# sch3.net
KiCad netlist of a schematic drawn in Altium Designer
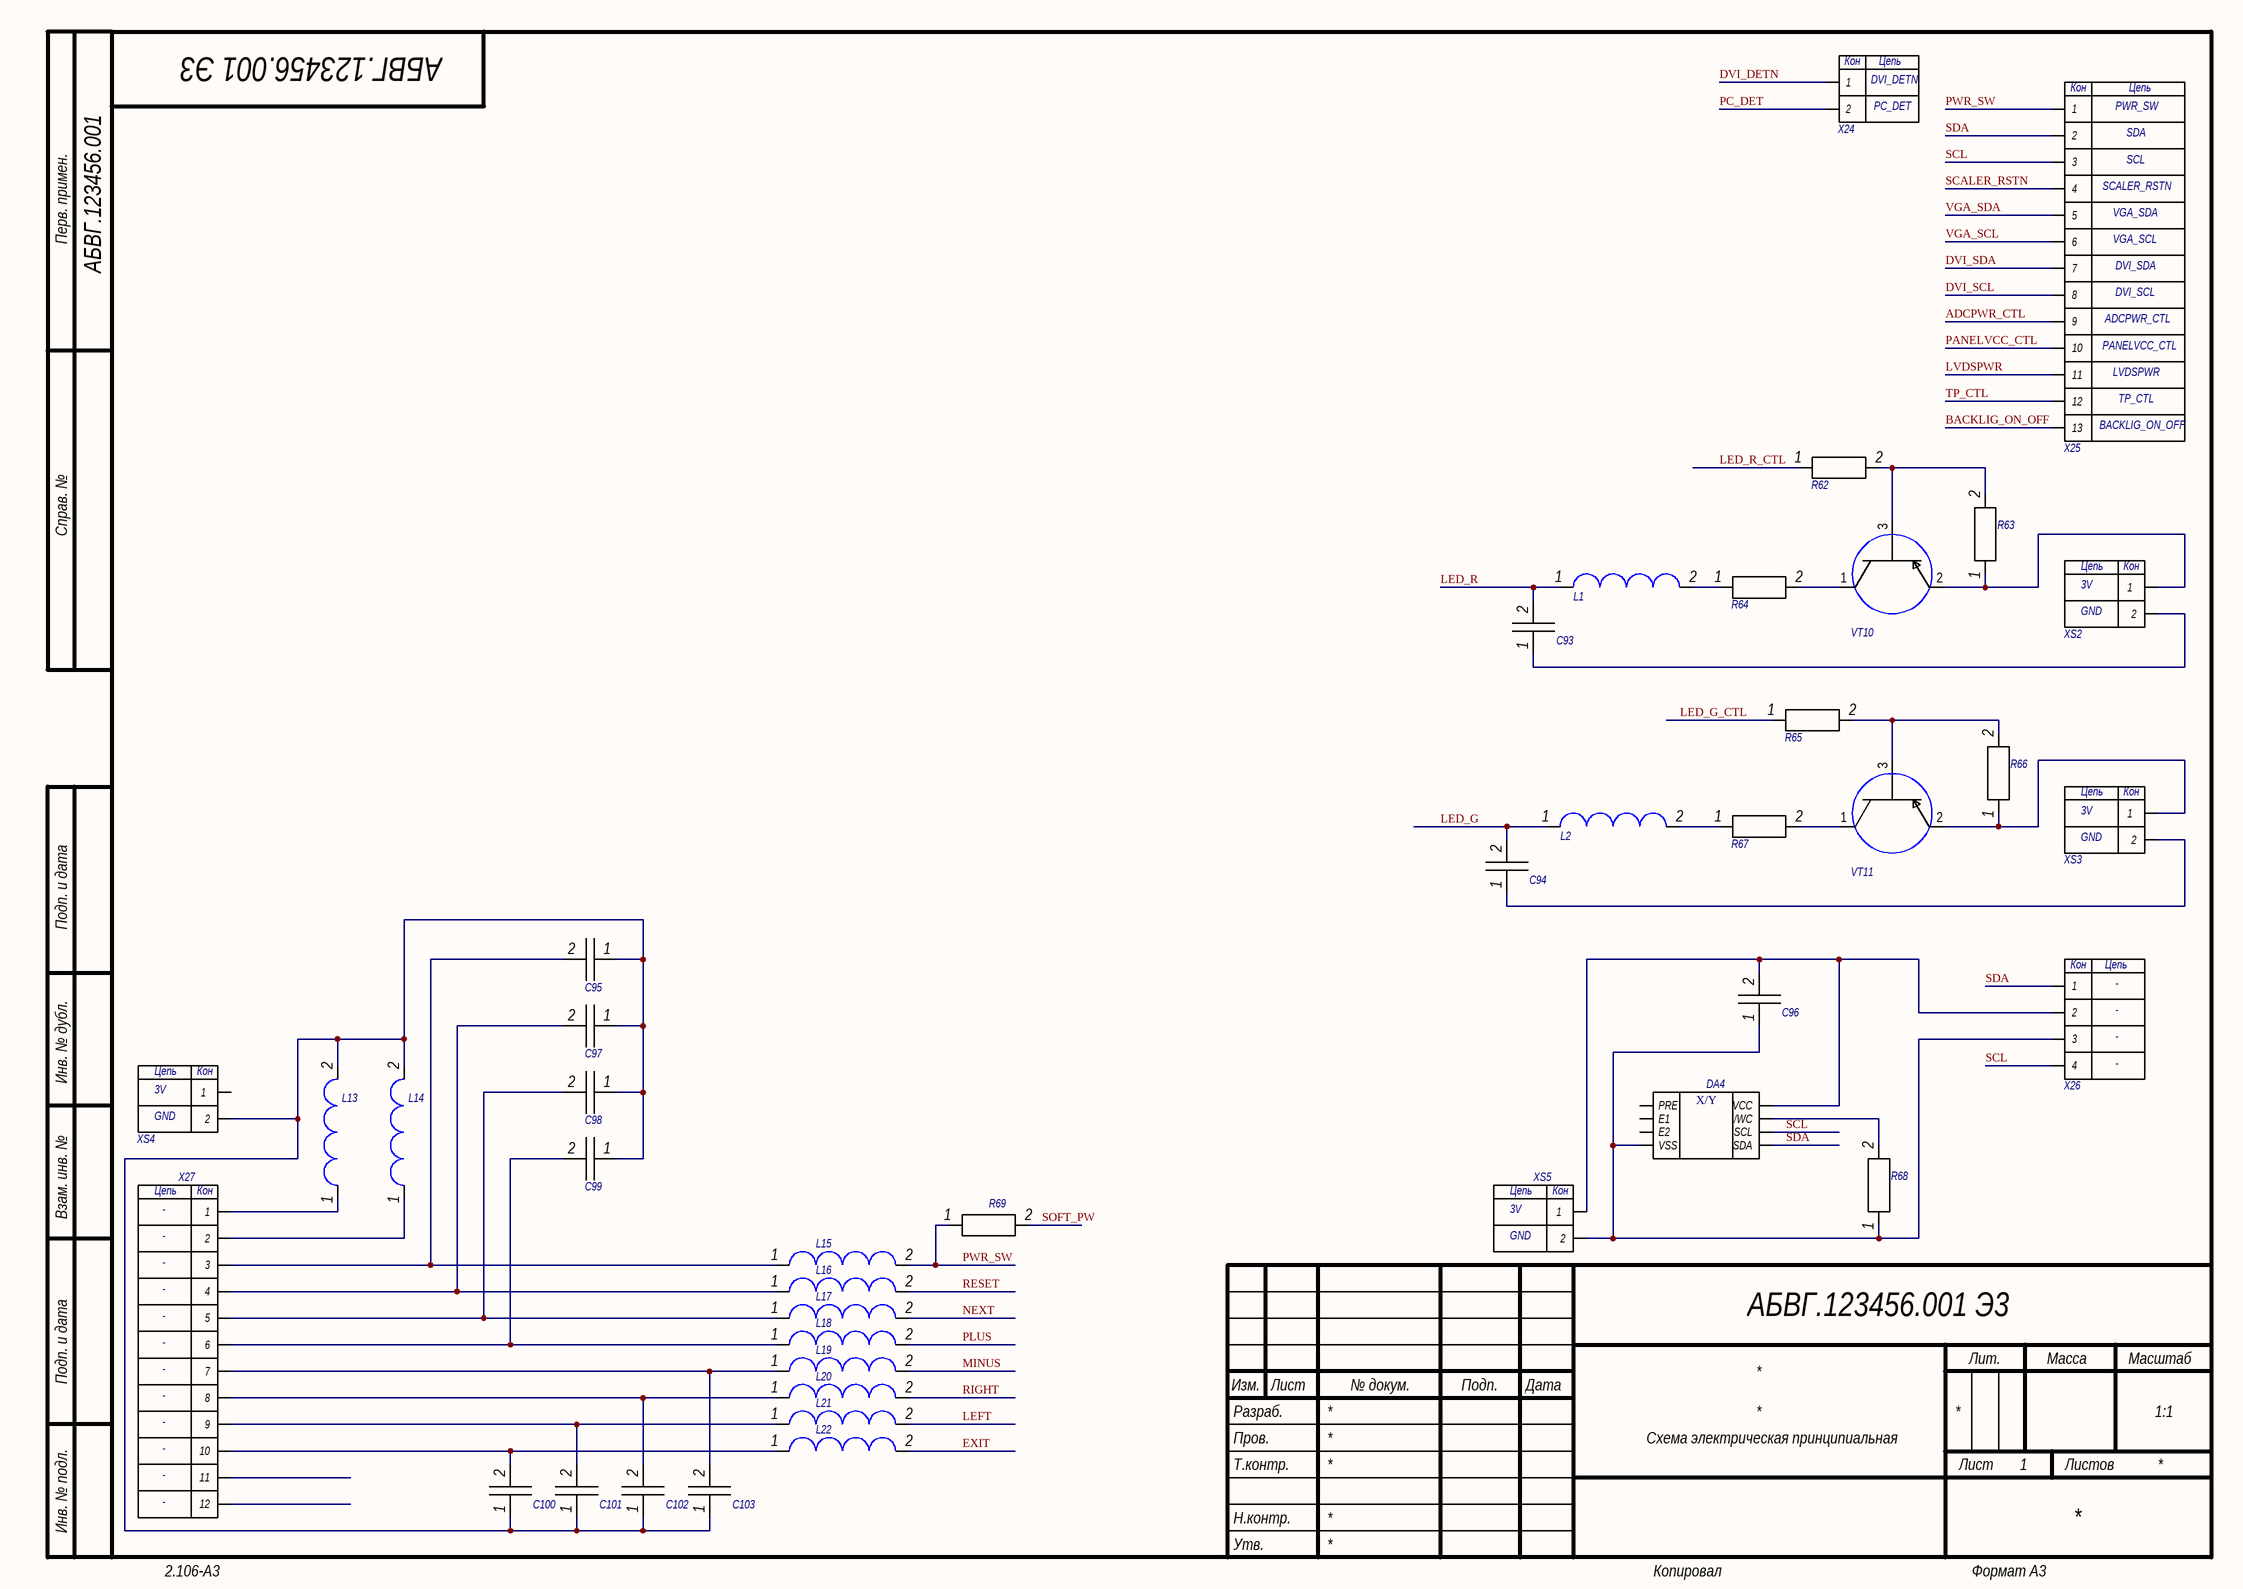
[diagram p0: sch3.SchDoc]

(export (version "E")
  (design (tool "Eeschema 10.0.6"))
  (components
    (comp (ref "C93")
      (value "*")
      (footprint "Capacitor 0805")
      (libsource (lib "k7shared") (part "Capacitor"))
    )
    (comp (ref "C94")
      (value "*")
      (footprint "Capacitor 0805")
      (libsource (lib "k7shared") (part "Capacitor"))
    )
    (comp (ref "C95")
      (value "*")
      (footprint "Capacitor 0805")
      (libsource (lib "k7shared") (part "Capacitor"))
    )
    (comp (ref "C96")
      (value "*")
      (footprint "Capacitor 0805")
      (libsource (lib "k7shared") (part "Capacitor"))
    )
    (comp (ref "C97")
      (value "*")
      (footprint "Capacitor 0805")
      (libsource (lib "k7shared") (part "Capacitor"))
    )
    (comp (ref "C98")
      (value "*")
      (footprint "Capacitor 0805")
      (libsource (lib "k7shared") (part "Capacitor"))
    )
    (comp (ref "C99")
      (value "*")
      (footprint "Capacitor 0805")
      (libsource (lib "k7shared") (part "Capacitor"))
    )
    (comp (ref "C100")
      (value "*")
      (footprint "Capacitor 0805")
      (libsource (lib "k7shared") (part "Capacitor"))
    )
    (comp (ref "C101")
      (value "*")
      (footprint "Capacitor 0805")
      (libsource (lib "k7shared") (part "Capacitor"))
    )
    (comp (ref "C102")
      (value "*")
      (footprint "Capacitor 0805")
      (libsource (lib "k7shared") (part "Capacitor"))
    )
    (comp (ref "C103")
      (value "*")
      (footprint "Capacitor 0805")
      (libsource (lib "k7shared") (part "Capacitor"))
    )
    (comp (ref "DA4") (value "*") (footprint "IC102") (libsource (lib "k7sch3") (part "IC102")))
    (comp (ref "L1") (value "*") (footprint "Inductor 2520") (libsource (lib "k7shared") (part "Inductor")))
    (comp (ref "L2") (value "*") (footprint "Inductor 2520") (libsource (lib "k7shared") (part "Inductor")))
    (comp (ref "L13") (value "*") (footprint "Inductor 2520") (libsource (lib "") (part "Inductor_1")))
    (comp (ref "L14") (value "*") (footprint "Inductor 2520") (libsource (lib "") (part "Inductor_1")))
    (comp (ref "L15") (value "*") (footprint "Inductor 2520") (libsource (lib "k7shared") (part "Inductor")))
    (comp (ref "L16") (value "*") (footprint "Inductor 2520") (libsource (lib "k7shared") (part "Inductor")))
    (comp (ref "L17") (value "*") (footprint "Inductor 2520") (libsource (lib "k7shared") (part "Inductor")))
    (comp (ref "L18") (value "*") (footprint "Inductor 2520") (libsource (lib "k7shared") (part "Inductor")))
    (comp (ref "L19") (value "*") (footprint "Inductor 2520") (libsource (lib "k7shared") (part "Inductor")))
    (comp (ref "L20") (value "*") (footprint "Inductor 2520") (libsource (lib "k7shared") (part "Inductor")))
    (comp (ref "L21") (value "*") (footprint "Inductor 2520") (libsource (lib "k7shared") (part "Inductor")))
    (comp (ref "L22") (value "*") (footprint "Inductor 2520") (libsource (lib "k7shared") (part "Inductor")))
    (comp (ref "R62") (value "*") (footprint "Resistor 1206") (libsource (lib "k7shared") (part "Resistor")))
    (comp (ref "R63") (value "*") (footprint "Resistor 1206") (libsource (lib "k7shared") (part "Resistor")))
    (comp (ref "R64") (value "*") (footprint "Resistor 1206") (libsource (lib "k7shared") (part "Resistor")))
    (comp (ref "R65") (value "*") (footprint "Resistor 1206") (libsource (lib "k7shared") (part "Resistor")))
    (comp (ref "R66") (value "*") (footprint "Resistor 1206") (libsource (lib "k7shared") (part "Resistor")))
    (comp (ref "R67") (value "*") (footprint "Resistor 1206") (libsource (lib "k7shared") (part "Resistor")))
    (comp (ref "R68") (value "*") (footprint "Resistor 1206") (libsource (lib "k7shared") (part "Resistor")))
    (comp (ref "R69") (value "*") (footprint "Resistor 1206") (libsource (lib "k7shared") (part "Resistor")))
    (comp (ref "VT10")
      (value "*")
      (footprint "Transistor 1")
      (libsource (lib "k7shared") (part "Transistor 2"))
    )
    (comp (ref "VT11")
      (value "*")
      (footprint "Transistor 1")
      (libsource (lib "k7shared") (part "Transistor 2"))
    )
    (comp (ref "X24") (value "*") (footprint "Inputs") (libsource (lib "k7sch3") (part "Inputs")))
    (comp (ref "X25") (value "*") (footprint "Outputs") (libsource (lib "k7sch3") (part "Outputs")))
    (comp (ref "X26") (value "*") (footprint "J102") (libsource (lib "k7sch3") (part "J102")))
    (comp (ref "X27") (value "*") (footprint "J101") (libsource (lib "k7sch3") (part "J101")))
    (comp (ref "XS2") (value "*") (footprint "VCC-GND") (libsource (lib "k7shared") (part "VCC-GND R")))
    (comp (ref "XS3") (value "*") (footprint "VCC-GND") (libsource (lib "k7shared") (part "VCC-GND R")))
    (comp (ref "XS4") (value "*") (footprint "VCC-GND") (libsource (lib "k7shared") (part "VCC-GND R")))
    (comp (ref "XS5") (value "*") (footprint "VCC-GND") (libsource (lib "k7shared") (part "VCC-GND R")))
  )
  (nets
    (net (code "1") (name "/ADCPWR_CTL") (class "Default")
      (node (ref "X25") (pin "9") (pinfunction "9_9") (pintype "passive"))
    )
    (net (code "2") (name "/BACKLIG_ON_OFF") (class "Default")
      (node (ref "X25") (pin "13") (pinfunction "13_13") (pintype "passive"))
    )
    (net (code "3") (name "/DVI_DETN") (class "Default")
      (node (ref "X24") (pin "1") (pinfunction "1_1") (pintype "passive"))
    )
    (net (code "4") (name "/DVI_SCL") (class "Default")
      (node (ref "X25") (pin "8") (pinfunction "8_8") (pintype "passive"))
    )
    (net (code "5") (name "/DVI_SDA") (class "Default")
      (node (ref "X25") (pin "7") (pinfunction "7_7") (pintype "passive"))
    )
    (net (code "6") (name "/EXIT") (class "Default")
      (node (ref "L22") (pin "2") (pinfunction "2_2") (pintype "passive"))
    )
    (net (code "7") (name "/LED_G") (class "Default")
      (node (ref "C94") (pin "2") (pinfunction "2_2") (pintype "passive"))
      (node (ref "L2") (pin "1") (pinfunction "1_1") (pintype "passive"))
    )
    (net (code "8") (name "/LED_G_CTL") (class "Default")
      (node (ref "R65") (pin "1") (pinfunction "1_1") (pintype "passive"))
    )
    (net (code "9") (name "/LED_R") (class "Default")
      (node (ref "C93") (pin "2") (pinfunction "2_2") (pintype "passive"))
      (node (ref "L1") (pin "1") (pinfunction "1_1") (pintype "passive"))
    )
    (net (code "10") (name "/LED_R_CTL") (class "Default")
      (node (ref "R62") (pin "1") (pinfunction "1_1") (pintype "passive"))
    )
    (net (code "11") (name "/LEFT") (class "Default")
      (node (ref "L21") (pin "2") (pinfunction "2_2") (pintype "passive"))
    )
    (net (code "12") (name "/LVDSPWR") (class "Default")
      (node (ref "X25") (pin "11") (pinfunction "11_11") (pintype "passive"))
    )
    (net (code "13") (name "/MINUS") (class "Default")
      (node (ref "L19") (pin "2") (pinfunction "2_2") (pintype "passive"))
    )
    (net (code "14") (name "/NEXT") (class "Default")
      (node (ref "L17") (pin "2") (pinfunction "2_2") (pintype "passive"))
    )
    (net (code "15") (name "/PANELVCC_CTL") (class "Default")
      (node (ref "X25") (pin "10") (pinfunction "10_10") (pintype "passive"))
    )
    (net (code "16") (name "/PC_DET") (class "Default")
      (node (ref "X24") (pin "2") (pinfunction "2_2") (pintype "passive"))
    )
    (net (code "17") (name "/PLUS") (class "Default")
      (node (ref "L18") (pin "2") (pinfunction "2_2") (pintype "passive"))
    )
    (net (code "18") (name "/PWR_SW") (class "Default")
      (node (ref "L15") (pin "2") (pinfunction "2_2") (pintype "passive"))
      (node (ref "R69") (pin "1") (pinfunction "1_1") (pintype "passive"))
      (node (ref "X25") (pin "1") (pinfunction "1_1") (pintype "passive"))
    )
    (net (code "19") (name "/RESET") (class "Default")
      (node (ref "L16") (pin "2") (pinfunction "2_2") (pintype "passive"))
    )
    (net (code "20") (name "/RIGHT") (class "Default")
      (node (ref "L20") (pin "2") (pinfunction "2_2") (pintype "passive"))
    )
    (net (code "21") (name "/SCALER_RSTN") (class "Default")
      (node (ref "X25") (pin "4") (pinfunction "4_4") (pintype "passive"))
    )
    (net (code "22") (name "/SCL") (class "Default")
      (node (ref "DA4") (pin "7") (pinfunction "SCL_7") (pintype "passive"))
      (node (ref "X25") (pin "3") (pinfunction "3_3") (pintype "passive"))
      (node (ref "X26") (pin "4") (pinfunction "4_4") (pintype "passive"))
    )
    (net (code "23") (name "/SDA") (class "Default")
      (node (ref "DA4") (pin "8") (pinfunction "SDA_8") (pintype "passive"))
      (node (ref "X25") (pin "2") (pinfunction "2_2") (pintype "passive"))
      (node (ref "X26") (pin "1") (pinfunction "1_1") (pintype "passive"))
    )
    (net (code "24") (name "/SOFT_PW") (class "Default")
      (node (ref "R69") (pin "2") (pinfunction "2_2") (pintype "passive"))
    )
    (net (code "25") (name "/TP_CTL") (class "Default")
      (node (ref "X25") (pin "12") (pinfunction "12_12") (pintype "passive"))
    )
    (net (code "26") (name "/VGA_SCL") (class "Default")
      (node (ref "X25") (pin "6") (pinfunction "6_6") (pintype "passive"))
    )
    (net (code "27") (name "/VGA_SDA") (class "Default")
      (node (ref "X25") (pin "5") (pinfunction "5_5") (pintype "passive"))
    )
    (net (code "28") (name "Net-(C93-Pad1)") (class "Default")
      (node (ref "C93") (pin "1") (pinfunction "1_1") (pintype "passive"))
      (node (ref "XS2") (pin "2") (pinfunction "2_2") (pintype "passive"))
    )
    (net (code "29") (name "Net-(C94-Pad1)") (class "Default")
      (node (ref "C94") (pin "1") (pinfunction "1_1") (pintype "passive"))
      (node (ref "XS3") (pin "2") (pinfunction "2_2") (pintype "passive"))
    )
    (net (code "30") (name "Net-(C95-Pad2)") (class "Default")
      (node (ref "C95") (pin "2") (pinfunction "2_2") (pintype "passive"))
      (node (ref "L15") (pin "1") (pinfunction "1_1") (pintype "passive"))
      (node (ref "X27") (pin "3") (pinfunction "3_3") (pintype "passive"))
    )
    (net (code "31") (name "Net-(C97-Pad2)") (class "Default")
      (node (ref "C97") (pin "2") (pinfunction "2_2") (pintype "passive"))
      (node (ref "L16") (pin "1") (pinfunction "1_1") (pintype "passive"))
      (node (ref "X27") (pin "4") (pinfunction "4_4") (pintype "passive"))
    )
    (net (code "32") (name "Net-(C98-Pad2)") (class "Default")
      (node (ref "C98") (pin "2") (pinfunction "2_2") (pintype "passive"))
      (node (ref "L17") (pin "1") (pinfunction "1_1") (pintype "passive"))
      (node (ref "X27") (pin "5") (pinfunction "5_5") (pintype "passive"))
    )
    (net (code "33") (name "Net-(C99-Pad2)") (class "Default")
      (node (ref "C99") (pin "2") (pinfunction "2_2") (pintype "passive"))
      (node (ref "L18") (pin "1") (pinfunction "1_1") (pintype "passive"))
      (node (ref "X27") (pin "6") (pinfunction "6_6") (pintype "passive"))
    )
    (net (code "34") (name "Net-(C100-Pad1)") (class "Default")
      (node (ref "C100") (pin "1") (pinfunction "1_1") (pintype "passive"))
      (node (ref "C101") (pin "1") (pinfunction "1_1") (pintype "passive"))
      (node (ref "C102") (pin "1") (pinfunction "1_1") (pintype "passive"))
      (node (ref "C103") (pin "1") (pinfunction "1_1") (pintype "passive"))
      (node (ref "C95") (pin "1") (pinfunction "1_1") (pintype "passive"))
      (node (ref "C97") (pin "1") (pinfunction "1_1") (pintype "passive"))
      (node (ref "C98") (pin "1") (pinfunction "1_1") (pintype "passive"))
      (node (ref "C99") (pin "1") (pinfunction "1_1") (pintype "passive"))
      (node (ref "L13") (pin "2") (pinfunction "2_2") (pintype "passive"))
      (node (ref "L14") (pin "2") (pinfunction "2_2") (pintype "passive"))
      (node (ref "XS4") (pin "2") (pinfunction "2_2") (pintype "passive"))
    )
    (net (code "35") (name "Net-(C100-Pad2)") (class "Default")
      (node (ref "C100") (pin "2") (pinfunction "2_2") (pintype "passive"))
      (node (ref "L22") (pin "1") (pinfunction "1_1") (pintype "passive"))
      (node (ref "X27") (pin "10") (pinfunction "10_10") (pintype "passive"))
    )
    (net (code "36") (name "Net-(C101-Pad2)") (class "Default")
      (node (ref "C101") (pin "2") (pinfunction "2_2") (pintype "passive"))
      (node (ref "L21") (pin "1") (pinfunction "1_1") (pintype "passive"))
      (node (ref "X27") (pin "9") (pinfunction "9_9") (pintype "passive"))
    )
    (net (code "37") (name "Net-(C102-Pad2)") (class "Default")
      (node (ref "C102") (pin "2") (pinfunction "2_2") (pintype "passive"))
      (node (ref "L20") (pin "1") (pinfunction "1_1") (pintype "passive"))
      (node (ref "X27") (pin "8") (pinfunction "8_8") (pintype "passive"))
    )
    (net (code "38") (name "Net-(C103-Pad2)") (class "Default")
      (node (ref "C103") (pin "2") (pinfunction "2_2") (pintype "passive"))
      (node (ref "L19") (pin "1") (pinfunction "1_1") (pintype "passive"))
      (node (ref "X27") (pin "7") (pinfunction "7_7") (pintype "passive"))
    )
    (net (code "39") (name "Net-(DA4-VCC)") (class "Default")
      (node (ref "C96") (pin "2") (pinfunction "2_2") (pintype "passive"))
      (node (ref "DA4") (pin "5") (pinfunction "VCC_5") (pintype "passive"))
      (node (ref "X26") (pin "2") (pinfunction "2_2") (pintype "passive"))
      (node (ref "XS5") (pin "1") (pinfunction "1_1") (pintype "passive"))
    )
    (net (code "40") (name "Net-(DA4-VSS)") (class "Default")
      (node (ref "C96") (pin "1") (pinfunction "1_1") (pintype "passive"))
      (node (ref "DA4") (pin "4") (pinfunction "VSS_4") (pintype "passive"))
      (node (ref "R68") (pin "1") (pinfunction "1_1") (pintype "passive"))
      (node (ref "X26") (pin "3") (pinfunction "3_3") (pintype "passive"))
      (node (ref "XS5") (pin "2") (pinfunction "2_2") (pintype "passive"))
    )
    (net (code "41") (name "Net-(DA4-{slash}WC)") (class "Default")
      (node (ref "DA4") (pin "6") (pinfunction "/WC_6") (pintype "passive"))
      (node (ref "R68") (pin "2") (pinfunction "2_2") (pintype "passive"))
    )
    (net (code "42") (name "Net-(L1-Pad2)") (class "Default")
      (node (ref "L1") (pin "2") (pinfunction "2_2") (pintype "passive"))
      (node (ref "R64") (pin "1") (pinfunction "1_1") (pintype "passive"))
    )
    (net (code "43") (name "Net-(L2-Pad2)") (class "Default")
      (node (ref "L2") (pin "2") (pinfunction "2_2") (pintype "passive"))
      (node (ref "R67") (pin "1") (pinfunction "1_1") (pintype "passive"))
    )
    (net (code "44") (name "Net-(L13-Pad1)") (class "Default")
      (node (ref "L13") (pin "1") (pinfunction "1_1") (pintype "passive"))
      (node (ref "X27") (pin "1") (pinfunction "1_1") (pintype "passive"))
    )
    (net (code "45") (name "Net-(L14-Pad1)") (class "Default")
      (node (ref "L14") (pin "1") (pinfunction "1_1") (pintype "passive"))
      (node (ref "X27") (pin "2") (pinfunction "2_2") (pintype "passive"))
    )
    (net (code "46") (name "Net-(VT10-BAZA)") (class "Default")
      (node (ref "R62") (pin "2") (pinfunction "2_2") (pintype "passive"))
      (node (ref "R63") (pin "2") (pinfunction "2_2") (pintype "passive"))
      (node (ref "VT10") (pin "3") (pinfunction "BAZA_3") (pintype "passive"))
    )
    (net (code "47") (name "Net-(VT10-EMITTER)") (class "Default")
      (node (ref "R63") (pin "1") (pinfunction "1_1") (pintype "passive"))
      (node (ref "VT10") (pin "2") (pinfunction "EMITTER_2") (pintype "passive"))
      (node (ref "XS2") (pin "1") (pinfunction "1_1") (pintype "passive"))
    )
    (net (code "48") (name "Net-(VT10-KOLLECTOR)") (class "Default")
      (node (ref "R64") (pin "2") (pinfunction "2_2") (pintype "passive"))
      (node (ref "VT10") (pin "1") (pinfunction "KOLLECTOR_1") (pintype "passive"))
    )
    (net (code "49") (name "Net-(VT11-BAZA)") (class "Default")
      (node (ref "R65") (pin "2") (pinfunction "2_2") (pintype "passive"))
      (node (ref "R66") (pin "2") (pinfunction "2_2") (pintype "passive"))
      (node (ref "VT11") (pin "3") (pinfunction "BAZA_3") (pintype "passive"))
    )
    (net (code "50") (name "Net-(VT11-EMITTER)") (class "Default")
      (node (ref "R66") (pin "1") (pinfunction "1_1") (pintype "passive"))
      (node (ref "VT11") (pin "2") (pinfunction "EMITTER_2") (pintype "passive"))
      (node (ref "XS3") (pin "1") (pinfunction "1_1") (pintype "passive"))
    )
    (net (code "51") (name "Net-(VT11-KOLLECTOR)") (class "Default")
      (node (ref "R67") (pin "2") (pinfunction "2_2") (pintype "passive"))
      (node (ref "VT11") (pin "1") (pinfunction "KOLLECTOR_1") (pintype "passive"))
    )
    (net (code "52") (name "unconnected-(DA4-E1-Pad2)") (class "Default")
      (node (ref "DA4") (pin "2") (pinfunction "E1_2") (pintype "passive"))
    )
    (net (code "53") (name "unconnected-(DA4-E2-Pad3)") (class "Default")
      (node (ref "DA4") (pin "3") (pinfunction "E2_3") (pintype "passive"))
    )
    (net (code "54") (name "unconnected-(DA4-PRE-Pad1)") (class "Default")
      (node (ref "DA4") (pin "1") (pinfunction "PRE_1") (pintype "passive"))
    )
    (net (code "55") (name "unconnected-(X27-Pad11)") (class "Default")
      (node (ref "X27") (pin "11") (pinfunction "11_11") (pintype "passive"))
    )
    (net (code "56") (name "unconnected-(X27-Pad12)") (class "Default")
      (node (ref "X27") (pin "12") (pinfunction "12_12") (pintype "passive"))
    )
    (net (code "57") (name "unconnected-(XS4-Pad1)") (class "Default")
      (node (ref "XS4") (pin "1") (pinfunction "1_1") (pintype "passive"))
    )
  )
)
